# 10AxisFeatherWingLE.net
KiCad netlist of a schematic drawn in EAGLE
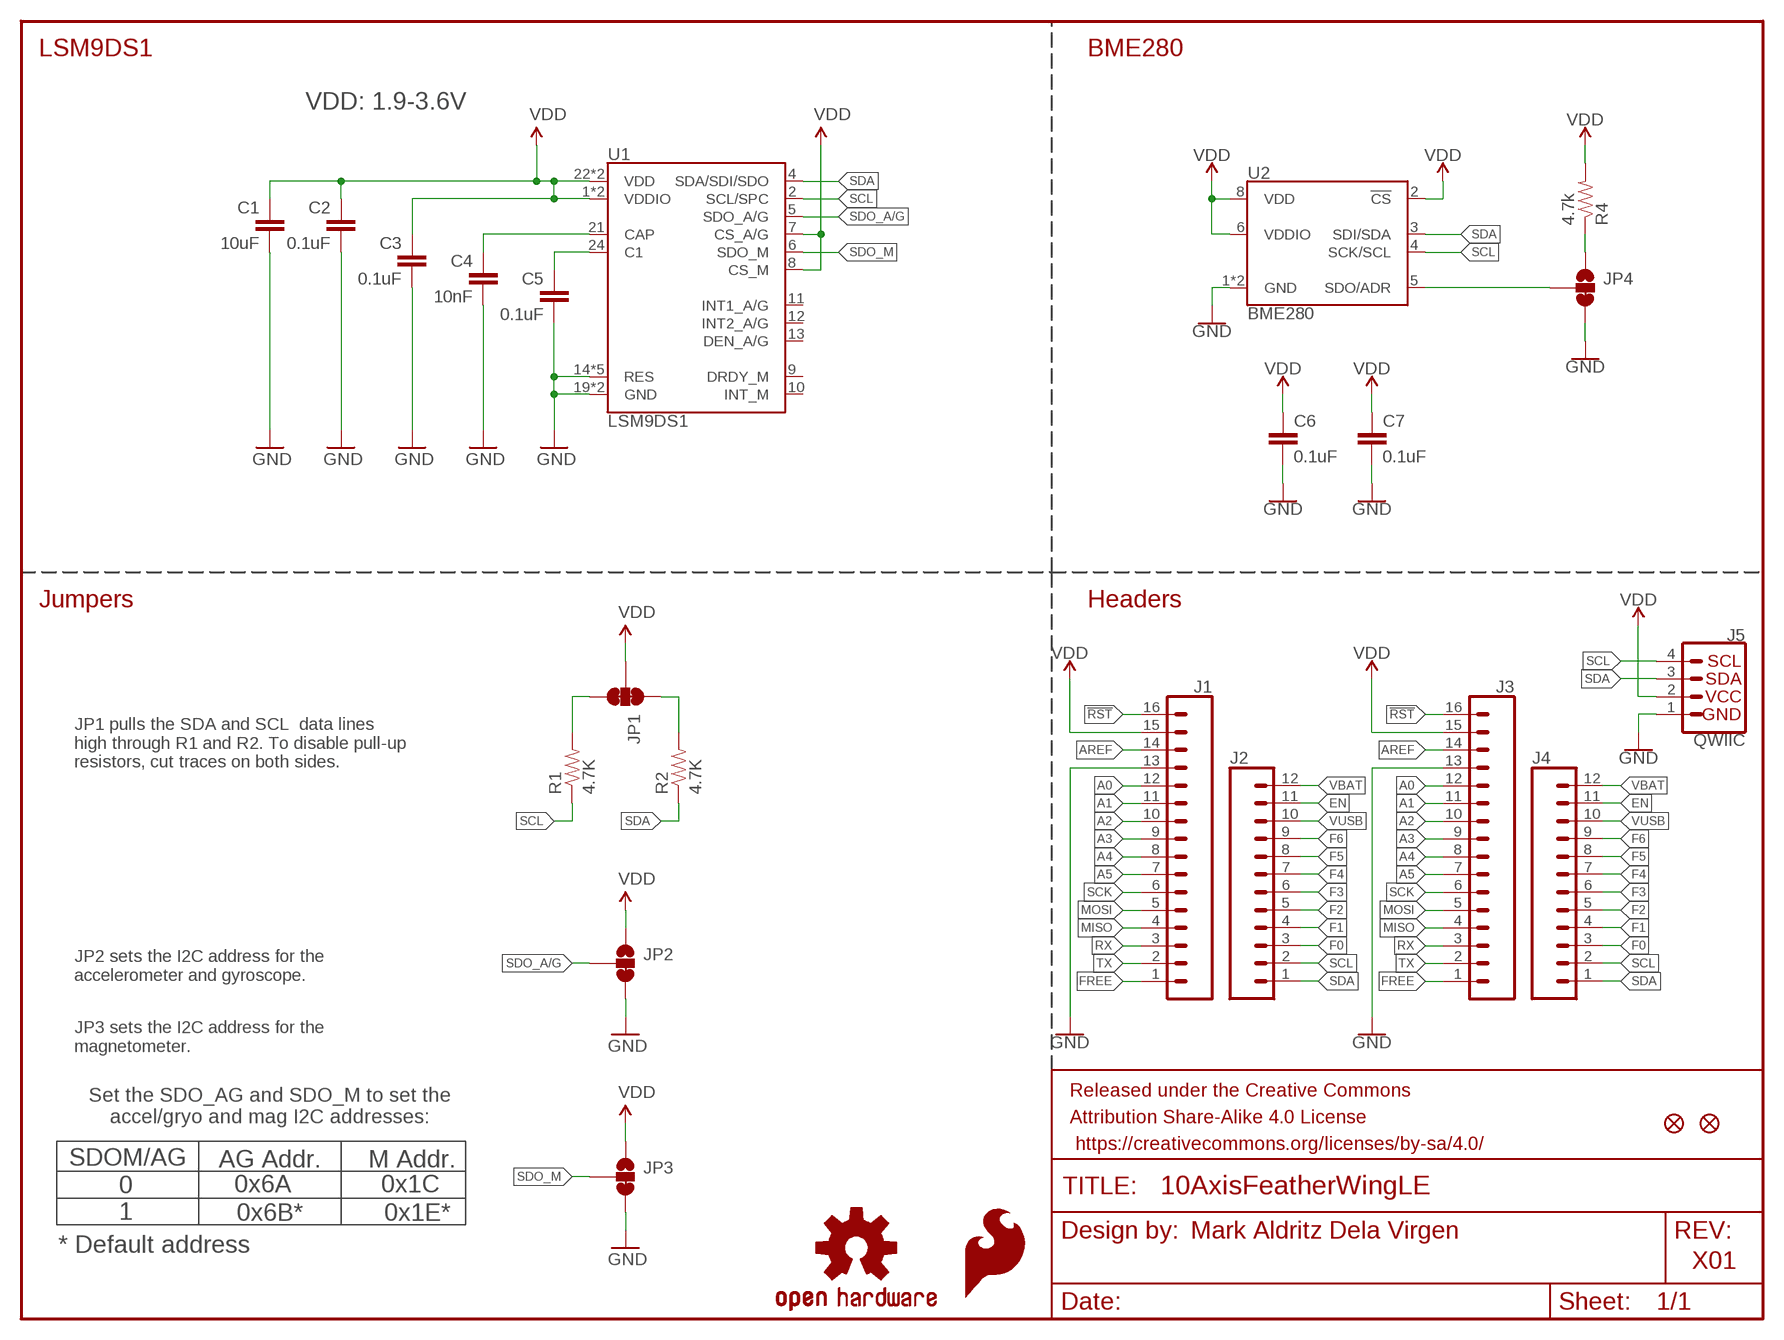
[diagram p0: schematic, sheet 1]

(export (version "E")
  (design (tool "Eeschema 10.0.6"))
  (components
    (comp (ref "C1")
      (value "10uF")
      (footprint "eagle-import:0603-CAP@1")
      (libsource (lib "eagle-import") (part "10UF-6.3V-20%(0603)"))
    )
    (comp (ref "C2")
      (value "0.1uF")
      (footprint "eagle-import:0603-CAP@1")
      (libsource (lib "eagle-import") (part "0.1UF-25V(+80/-20%)(0603)"))
    )
    (comp (ref "C3")
      (value "0.1uF")
      (footprint "eagle-import:0603-CAP@1")
      (libsource (lib "eagle-import") (part "0.1UF-25V(+80/-20%)(0603)"))
    )
    (comp (ref "C4")
      (value "10nF")
      (footprint "eagle-import:0603-CAP@1")
      (libsource (lib "eagle-import") (part "10NF/10000PF-50V-10%(0603)"))
    )
    (comp (ref "C5")
      (value "0.1uF")
      (footprint "eagle-import:0603-CAP@1")
      (libsource (lib "eagle-import") (part "0.1UF-25V(+80/-20%)(0603)"))
    )
    (comp (ref "C6")
      (value "0.1uF")
      (footprint "eagle-import:0603")
      (libsource (lib "eagle-import") (part "0.1UF-0603-25V-(+80/-20%)"))
    )
    (comp (ref "C7")
      (value "0.1uF")
      (footprint "eagle-import:0603")
      (libsource (lib "eagle-import") (part "0.1UF-0603-25V-(+80/-20%)"))
    )
    (comp (ref "FD3")
      (value "FIDUCIALUFIDUCIAL")
      (footprint "eagle-import:MICRO-FIDUCIAL")
      (libsource (lib "eagle-import") (part "FIDUCIALUFIDUCIAL"))
    )
    (comp (ref "FD4")
      (value "FIDUCIALUFIDUCIAL")
      (footprint "eagle-import:MICRO-FIDUCIAL")
      (libsource (lib "eagle-import") (part "FIDUCIALUFIDUCIAL"))
    )
    (comp (ref "FRAME1")
      (value "FRAME-LETTER")
      (footprint "eagle-import:CREATIVE_COMMONS")
      (libsource (lib "eagle-import") (part "FRAME-LETTER"))
    )
    (comp (ref "J1")
      (value "CONN_161X16_NO_SILK")
      (footprint "eagle-import:1X16_NO_SILK")
      (libsource (lib "eagle-import") (part "CONN_161X16_NO_SILK"))
    )
    (comp (ref "J2")
      (value "CONN_12NO_SILK")
      (footprint "eagle-import:1X12_NO_SILK")
      (libsource (lib "eagle-import") (part "CONN_12NO_SILK"))
    )
    (comp (ref "J3")
      (value "CONN_161X16_NO_SILK")
      (footprint "eagle-import:1X16_NO_SILK")
      (libsource (lib "eagle-import") (part "CONN_161X16_NO_SILK"))
    )
    (comp (ref "J4")
      (value "CONN_12NO_SILK")
      (footprint "eagle-import:1X12_NO_SILK")
      (libsource (lib "eagle-import") (part "CONN_12NO_SILK"))
    )
    (comp (ref "J5")
      (value "QWIIC")
      (footprint "eagle-import:1X04_1MM_RA")
      (libsource (lib "eagle-import") (part "I2C_STANDARDQWIIC"))
    )
    (comp (ref "JP1")
      (value "JUMPER-SMT_3_2-NC_TRACE_SILK")
      (footprint "eagle-import:SMT-JUMPER_3_2-NC_TRACE_SILK")
      (libsource (lib "eagle-import") (part "JUMPER-SMT_3_2-NC_TRACE_SILK"))
    )
    (comp (ref "JP2")
      (value "JUMPER-SMT_3_1-NC_TRACE_SILK")
      (footprint "eagle-import:SMT-JUMPER_3_1-NC_TRACE_SILK")
      (libsource (lib "eagle-import") (part "JUMPER-SMT_3_1-NC_TRACE_SILK"))
    )
    (comp (ref "JP3")
      (value "JUMPER-SMT_3_1-NC_TRACE_SILK")
      (footprint "eagle-import:SMT-JUMPER_3_1-NC_TRACE_SILK")
      (libsource (lib "eagle-import") (part "JUMPER-SMT_3_1-NC_TRACE_SILK"))
    )
    (comp (ref "JP4")
      (value "JUMPER-SMT_3_1-NC_TRACE_SILK")
      (footprint "eagle-import:SMT-JUMPER_3_1-NC_TRACE_SILK")
      (libsource (lib "eagle-import") (part "JUMPER-SMT_3_1-NC_TRACE_SILK"))
    )
    (comp (ref "LOGO1")
      (value "SFE_LOGO_FLAME.1_INCH")
      (footprint "eagle-import:SFE_LOGO_FLAME_.1")
      (libsource (lib "eagle-import") (part "SFE_LOGO_FLAME.1_INCH"))
    )
    (comp (ref "LOGO3")
      (value "OSHW-LOGOMINI")
      (footprint "eagle-import:OSHW-LOGO-MINI")
      (libsource (lib "eagle-import") (part "OSHW-LOGOMINI"))
    )
    (comp (ref "R1")
      (value "4.7K")
      (footprint "eagle-import:0603-RES")
      (libsource (lib "eagle-import") (part "4.7KOHM-1/10W-1%(0603)"))
    )
    (comp (ref "R2")
      (value "4.7K")
      (footprint "eagle-import:0603-RES")
      (libsource (lib "eagle-import") (part "4.7KOHM-1/10W-1%(0603)"))
    )
    (comp (ref "R4")
      (value "4.7k")
      (footprint "eagle-import:0603")
      (libsource (lib "eagle-import") (part "4.7KOHM-0603-1/10W-1%"))
    )
    (comp (ref "U1")
      (value "LSM9DS1")
      (footprint "eagle-import:LGA24-8X4")
      (libsource (lib "eagle-import") (part "LSM9DS1"))
    )
    (comp (ref "U2")
      (value "BME280")
      (footprint "eagle-import:LGA-8-2.5X2.5")
      (libsource (lib "eagle-import") (part "BME280"))
    )
  )
  (nets
    (net (code "1") (name "/~{RST}") (class "Default")
      (node (ref "J1") (pin "16") (pinfunction "16_16") (pintype "passive"))
      (node (ref "J3") (pin "16") (pinfunction "16_16") (pintype "passive"))
    )
    (net (code "2") (name "A0") (class "Default")
      (node (ref "J1") (pin "12") (pinfunction "12_12") (pintype "passive"))
      (node (ref "J3") (pin "12") (pinfunction "12_12") (pintype "passive"))
    )
    (net (code "3") (name "A1") (class "Default")
      (node (ref "J1") (pin "11") (pinfunction "11_11") (pintype "passive"))
      (node (ref "J3") (pin "11") (pinfunction "11_11") (pintype "passive"))
    )
    (net (code "4") (name "A2") (class "Default")
      (node (ref "J1") (pin "10") (pinfunction "10_10") (pintype "passive"))
      (node (ref "J3") (pin "10") (pinfunction "10_10") (pintype "passive"))
    )
    (net (code "5") (name "A3") (class "Default")
      (node (ref "J1") (pin "9") (pinfunction "9_9") (pintype "passive"))
      (node (ref "J3") (pin "9") (pinfunction "9_9") (pintype "passive"))
    )
    (net (code "6") (name "A4") (class "Default")
      (node (ref "J1") (pin "8") (pinfunction "8_8") (pintype "passive"))
      (node (ref "J3") (pin "8") (pinfunction "8_8") (pintype "passive"))
    )
    (net (code "7") (name "A5") (class "Default")
      (node (ref "J1") (pin "7") (pinfunction "7_7") (pintype "passive"))
      (node (ref "J3") (pin "7") (pinfunction "7_7") (pintype "passive"))
    )
    (net (code "8") (name "AREF") (class "Default")
      (node (ref "J1") (pin "14") (pinfunction "14_14") (pintype "passive"))
      (node (ref "J3") (pin "14") (pinfunction "14_14") (pintype "passive"))
    )
    (net (code "9") (name "EN") (class "Default")
      (node (ref "J2") (pin "11") (pinfunction "11_11") (pintype "passive"))
      (node (ref "J4") (pin "11") (pinfunction "11_11") (pintype "passive"))
    )
    (net (code "10") (name "F0") (class "Default")
      (node (ref "J2") (pin "3") (pinfunction "3_3") (pintype "passive"))
      (node (ref "J4") (pin "3") (pinfunction "3_3") (pintype "passive"))
    )
    (net (code "11") (name "F1") (class "Default")
      (node (ref "J2") (pin "4") (pinfunction "4_4") (pintype "passive"))
      (node (ref "J4") (pin "4") (pinfunction "4_4") (pintype "passive"))
    )
    (net (code "12") (name "F2") (class "Default")
      (node (ref "J2") (pin "5") (pinfunction "5_5") (pintype "passive"))
      (node (ref "J4") (pin "5") (pinfunction "5_5") (pintype "passive"))
    )
    (net (code "13") (name "F3") (class "Default")
      (node (ref "J2") (pin "6") (pinfunction "6_6") (pintype "passive"))
      (node (ref "J4") (pin "6") (pinfunction "6_6") (pintype "passive"))
    )
    (net (code "14") (name "F4") (class "Default")
      (node (ref "J2") (pin "7") (pinfunction "7_7") (pintype "passive"))
      (node (ref "J4") (pin "7") (pinfunction "7_7") (pintype "passive"))
    )
    (net (code "15") (name "F5") (class "Default")
      (node (ref "J2") (pin "8") (pinfunction "8_8") (pintype "passive"))
      (node (ref "J4") (pin "8") (pinfunction "8_8") (pintype "passive"))
    )
    (net (code "16") (name "F6") (class "Default")
      (node (ref "J2") (pin "9") (pinfunction "9_9") (pintype "passive"))
      (node (ref "J4") (pin "9") (pinfunction "9_9") (pintype "passive"))
    )
    (net (code "17") (name "FREE") (class "Default")
      (node (ref "J1") (pin "1") (pinfunction "1_1") (pintype "passive"))
      (node (ref "J3") (pin "1") (pinfunction "1_1") (pintype "passive"))
    )
    (net (code "18") (name "GND") (class "Default")
      (node (ref "C1") (pin "2") (pinfunction "2_2") (pintype "passive"))
      (node (ref "C2") (pin "2") (pinfunction "2_2") (pintype "passive"))
      (node (ref "C3") (pin "2") (pinfunction "2_2") (pintype "passive"))
      (node (ref "C4") (pin "2") (pinfunction "2_2") (pintype "passive"))
      (node (ref "C5") (pin "2") (pinfunction "2_2") (pintype "passive"))
      (node (ref "C6") (pin "2") (pinfunction "2_2") (pintype "passive"))
      (node (ref "C7") (pin "2") (pinfunction "2_2") (pintype "passive"))
      (node (ref "J1") (pin "13") (pinfunction "13_13") (pintype "passive"))
      (node (ref "J3") (pin "13") (pinfunction "13_13") (pintype "passive"))
      (node (ref "J5") (pin "1") (pinfunction "1_1") (pintype "power_in"))
      (node (ref "JP2") (pin "3") (pinfunction "3_3") (pintype "passive"))
      (node (ref "JP3") (pin "3") (pinfunction "3_3") (pintype "passive"))
      (node (ref "JP4") (pin "3") (pinfunction "3_3") (pintype "passive"))
      (node (ref "U1") (pin "14") (pinfunction "RES_14") (pintype "bidirectional"))
      (node (ref "U1") (pin "15") (pinfunction "RES_15") (pintype "bidirectional"))
      (node (ref "U1") (pin "16") (pinfunction "RES_16") (pintype "bidirectional"))
      (node (ref "U1") (pin "17") (pinfunction "RES_17") (pintype "bidirectional"))
      (node (ref "U1") (pin "18") (pinfunction "RES_18") (pintype "bidirectional"))
      (node (ref "U1") (pin "19") (pinfunction "GND_19") (pintype "bidirectional"))
      (node (ref "U1") (pin "20") (pinfunction "GND_20") (pintype "bidirectional"))
      (node (ref "U2") (pin "1") (pinfunction "GND_1") (pintype "bidirectional"))
      (node (ref "U2") (pin "7") (pinfunction "GND_7") (pintype "bidirectional"))
    )
    (net (code "19") (name "MISO") (class "Default")
      (node (ref "J1") (pin "4") (pinfunction "4_4") (pintype "passive"))
      (node (ref "J3") (pin "4") (pinfunction "4_4") (pintype "passive"))
    )
    (net (code "20") (name "MOSI") (class "Default")
      (node (ref "J1") (pin "5") (pinfunction "5_5") (pintype "passive"))
      (node (ref "J3") (pin "5") (pinfunction "5_5") (pintype "passive"))
    )
    (net (code "21") (name "Net-(JP1-Pad1)") (class "Default")
      (node (ref "JP1") (pin "1") (pinfunction "1_1") (pintype "passive"))
      (node (ref "R2") (pin "2") (pinfunction "2_2") (pintype "passive"))
    )
    (net (code "22") (name "Net-(JP1-Pad3)") (class "Default")
      (node (ref "JP1") (pin "3") (pinfunction "3_3") (pintype "passive"))
      (node (ref "R1") (pin "2") (pinfunction "2_2") (pintype "passive"))
    )
    (net (code "23") (name "Net-(JP4-Pad1)") (class "Default")
      (node (ref "JP4") (pin "1") (pinfunction "1_1") (pintype "passive"))
      (node (ref "R4") (pin "1") (pinfunction "1_1") (pintype "passive"))
    )
    (net (code "24") (name "Net-(U1-C1)") (class "Default")
      (node (ref "C5") (pin "1") (pinfunction "1_1") (pintype "passive"))
      (node (ref "U1") (pin "24") (pinfunction "C1_24") (pintype "bidirectional"))
    )
    (net (code "25") (name "Net-(U1-CAP)") (class "Default")
      (node (ref "C4") (pin "1") (pinfunction "1_1") (pintype "passive"))
      (node (ref "U1") (pin "21") (pinfunction "CAP_21") (pintype "bidirectional"))
    )
    (net (code "26") (name "Net-(U2-SDO{slash}ADR)") (class "Default")
      (node (ref "JP4") (pin "2") (pinfunction "2_2") (pintype "passive"))
      (node (ref "U2") (pin "5") (pinfunction "SDO/ADR_5") (pintype "bidirectional"))
    )
    (net (code "27") (name "RX") (class "Default")
      (node (ref "J1") (pin "3") (pinfunction "3_3") (pintype "passive"))
      (node (ref "J3") (pin "3") (pinfunction "3_3") (pintype "passive"))
    )
    (net (code "28") (name "SCK") (class "Default")
      (node (ref "J1") (pin "6") (pinfunction "6_6") (pintype "passive"))
      (node (ref "J3") (pin "6") (pinfunction "6_6") (pintype "passive"))
    )
    (net (code "29") (name "SCL") (class "Default")
      (node (ref "J2") (pin "2") (pinfunction "2_2") (pintype "passive"))
      (node (ref "J4") (pin "2") (pinfunction "2_2") (pintype "passive"))
      (node (ref "J5") (pin "4") (pinfunction "4_4") (pintype "passive"))
      (node (ref "R1") (pin "1") (pinfunction "1_1") (pintype "passive"))
      (node (ref "U1") (pin "2") (pinfunction "SCL/SPC_2") (pintype "bidirectional"))
      (node (ref "U2") (pin "4") (pinfunction "SCK/SCL_4") (pintype "bidirectional"))
    )
    (net (code "30") (name "SDA") (class "Default")
      (node (ref "J2") (pin "1") (pinfunction "1_1") (pintype "passive"))
      (node (ref "J4") (pin "1") (pinfunction "1_1") (pintype "passive"))
      (node (ref "J5") (pin "3") (pinfunction "3_3") (pintype "passive"))
      (node (ref "R2") (pin "1") (pinfunction "1_1") (pintype "passive"))
      (node (ref "U1") (pin "4") (pinfunction "SDA/SDI/SDO_4") (pintype "bidirectional"))
      (node (ref "U2") (pin "3") (pinfunction "SDI/SDA_3") (pintype "bidirectional"))
    )
    (net (code "31") (name "SDO_A{slash}G") (class "Default")
      (node (ref "JP2") (pin "2") (pinfunction "2_2") (pintype "passive"))
      (node (ref "U1") (pin "5") (pinfunction "SDO_A/G_5") (pintype "bidirectional"))
    )
    (net (code "32") (name "SDO_M") (class "Default")
      (node (ref "JP3") (pin "2") (pinfunction "2_2") (pintype "passive"))
      (node (ref "U1") (pin "6") (pinfunction "SDO_M_6") (pintype "bidirectional"))
    )
    (net (code "33") (name "TX") (class "Default")
      (node (ref "J1") (pin "2") (pinfunction "2_2") (pintype "passive"))
      (node (ref "J3") (pin "2") (pinfunction "2_2") (pintype "passive"))
    )
    (net (code "34") (name "VBAT") (class "Default")
      (node (ref "J2") (pin "12") (pinfunction "12_12") (pintype "passive"))
      (node (ref "J4") (pin "12") (pinfunction "12_12") (pintype "passive"))
    )
    (net (code "35") (name "VDD") (class "Default")
      (node (ref "C1") (pin "1") (pinfunction "1_1") (pintype "passive"))
      (node (ref "C2") (pin "1") (pinfunction "1_1") (pintype "passive"))
      (node (ref "C3") (pin "1") (pinfunction "1_1") (pintype "passive"))
      (node (ref "C6") (pin "1") (pinfunction "1_1") (pintype "passive"))
      (node (ref "C7") (pin "1") (pinfunction "1_1") (pintype "passive"))
      (node (ref "J1") (pin "15") (pinfunction "15_15") (pintype "passive"))
      (node (ref "J3") (pin "15") (pinfunction "15_15") (pintype "passive"))
      (node (ref "J5") (pin "2") (pinfunction "2_2") (pintype "power_in"))
      (node (ref "JP1") (pin "2") (pinfunction "2_2") (pintype "passive"))
      (node (ref "JP2") (pin "1") (pinfunction "1_1") (pintype "passive"))
      (node (ref "JP3") (pin "1") (pinfunction "1_1") (pintype "passive"))
      (node (ref "R4") (pin "2") (pinfunction "2_2") (pintype "passive"))
      (node (ref "U1") (pin "1") (pinfunction "VDDIO_1") (pintype "bidirectional"))
      (node (ref "U1") (pin "22") (pinfunction "VDD_22") (pintype "bidirectional"))
      (node (ref "U1") (pin "23") (pinfunction "VDD_23") (pintype "bidirectional"))
      (node (ref "U1") (pin "3") (pinfunction "VDDIO_3") (pintype "bidirectional"))
      (node (ref "U1") (pin "7") (pinfunction "CS_A/G_7") (pintype "bidirectional"))
      (node (ref "U1") (pin "8") (pinfunction "CS_M_8") (pintype "bidirectional"))
      (node (ref "U2") (pin "2") (pinfunction "~{CS}_2") (pintype "bidirectional"))
      (node (ref "U2") (pin "6") (pinfunction "VDDIO_6") (pintype "bidirectional"))
      (node (ref "U2") (pin "8") (pinfunction "VDD_8") (pintype "bidirectional"))
    )
    (net (code "36") (name "VUSB") (class "Default")
      (node (ref "J2") (pin "10") (pinfunction "10_10") (pintype "passive"))
      (node (ref "J4") (pin "10") (pinfunction "10_10") (pintype "passive"))
    )
    (net (code "37") (name "unconnected-(U1-DEN_A{slash}G-Pad13)") (class "Default")
      (node (ref "U1") (pin "13") (pinfunction "DEN_A/G_13") (pintype "bidirectional"))
    )
    (net (code "38") (name "unconnected-(U1-DRDY_M-Pad9)") (class "Default")
      (node (ref "U1") (pin "9") (pinfunction "DRDY_M_9") (pintype "bidirectional"))
    )
    (net (code "39") (name "unconnected-(U1-INT1_A{slash}G-Pad11)") (class "Default")
      (node (ref "U1") (pin "11") (pinfunction "INT1_A/G_11") (pintype "bidirectional"))
    )
    (net (code "40") (name "unconnected-(U1-INT2_A{slash}G-Pad12)") (class "Default")
      (node (ref "U1") (pin "12") (pinfunction "INT2_A/G_12") (pintype "bidirectional"))
    )
    (net (code "41") (name "unconnected-(U1-INT_M-Pad10)") (class "Default")
      (node (ref "U1") (pin "10") (pinfunction "INT_M_10") (pintype "bidirectional"))
    )
  )
)
